# JPhan_Board3.net
KiCad netlist of a schematic drawn in EAGLE
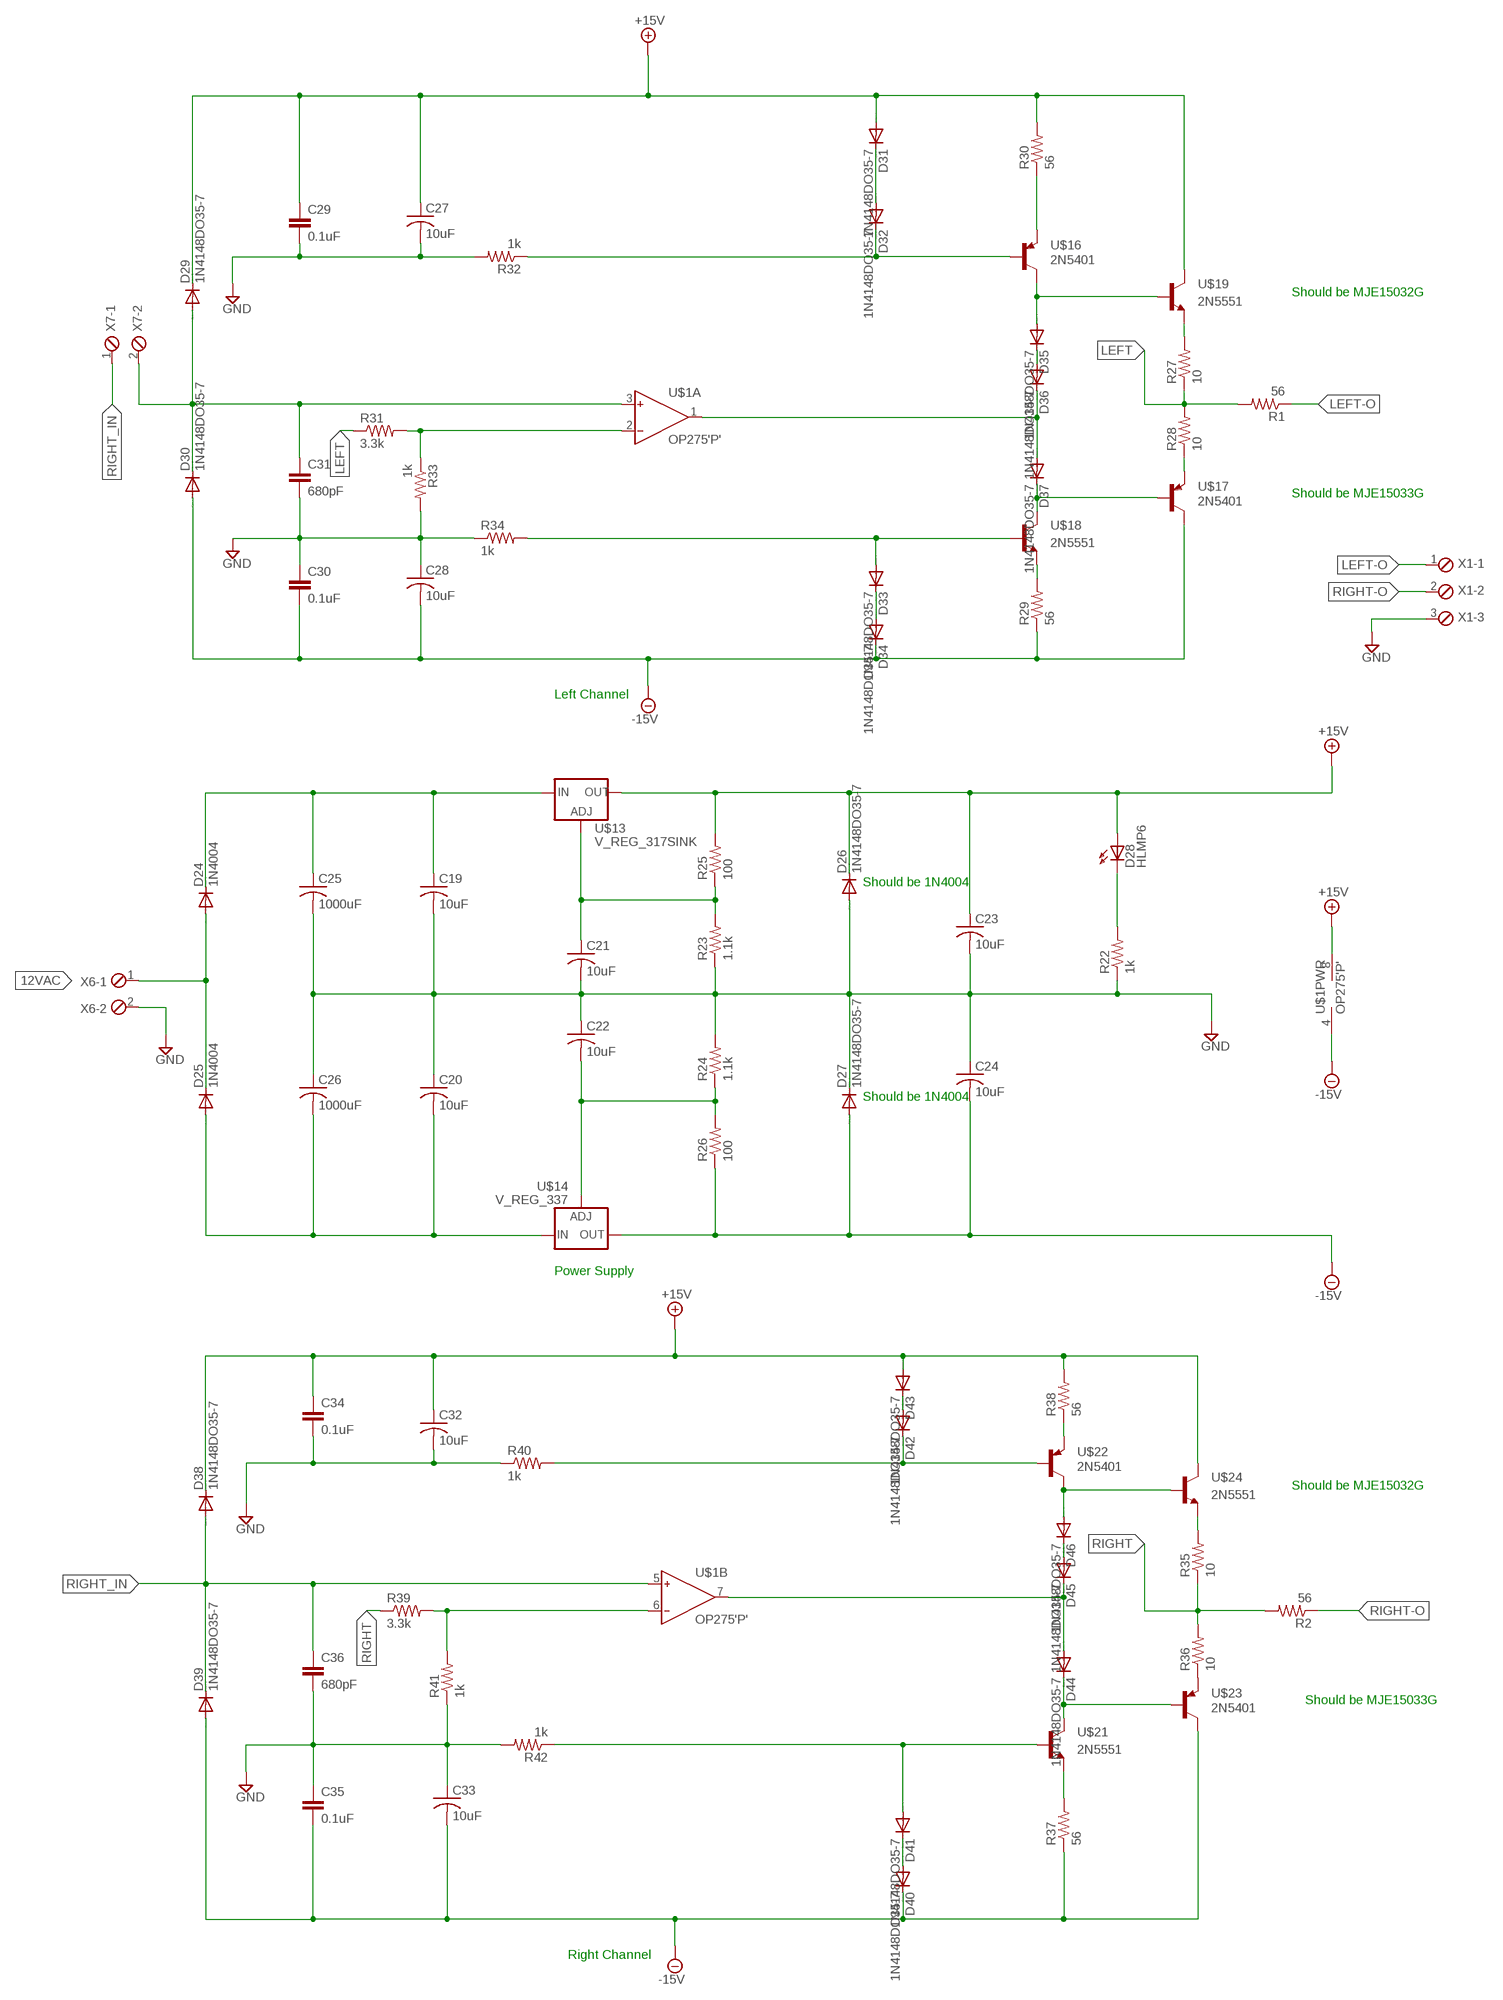
[diagram p0: schematic, sheet 1]

(export (version "E")
  (design (tool "Eeschema 10.0.6"))
  (components
    (comp (ref "C19")
      (value "10uF")
      (footprint "eagle-import:C025-030X050")
      (libsource (lib "eagle-import") (part "C-US025-030X050"))
    )
    (comp (ref "C20")
      (value "10uF")
      (footprint "eagle-import:C025-030X050")
      (libsource (lib "eagle-import") (part "C-US025-030X050"))
    )
    (comp (ref "C21")
      (value "10uF")
      (footprint "eagle-import:C025-030X050")
      (libsource (lib "eagle-import") (part "C-US025-030X050"))
    )
    (comp (ref "C22")
      (value "10uF")
      (footprint "eagle-import:C025-030X050")
      (libsource (lib "eagle-import") (part "C-US025-030X050"))
    )
    (comp (ref "C23")
      (value "10uF")
      (footprint "eagle-import:C025-030X050")
      (libsource (lib "eagle-import") (part "C-US025-030X050"))
    )
    (comp (ref "C24")
      (value "10uF")
      (footprint "eagle-import:C025-030X050")
      (libsource (lib "eagle-import") (part "C-US025-030X050"))
    )
    (comp (ref "C25")
      (value "1000uF")
      (footprint "eagle-import:C050-045X075")
      (libsource (lib "eagle-import") (part "C-US050-045X075"))
    )
    (comp (ref "C26")
      (value "1000uF")
      (footprint "eagle-import:C050-045X075")
      (libsource (lib "eagle-import") (part "C-US050-045X075"))
    )
    (comp (ref "C27")
      (value "10uF")
      (footprint "eagle-import:C025-030X050")
      (libsource (lib "eagle-import") (part "C-US025-030X050"))
    )
    (comp (ref "C28")
      (value "10uF")
      (footprint "eagle-import:C025-030X050")
      (libsource (lib "eagle-import") (part "C-US025-030X050"))
    )
    (comp (ref "C29")
      (value "0.1uF")
      (footprint "eagle-import:C025-024X044")
      (libsource (lib "eagle-import") (part "C-EU025-024X044"))
    )
    (comp (ref "C30")
      (value "0.1uF")
      (footprint "eagle-import:C025-024X044")
      (libsource (lib "eagle-import") (part "C-EU025-024X044"))
    )
    (comp (ref "C31")
      (value "680pF")
      (footprint "eagle-import:C025-024X044")
      (libsource (lib "eagle-import") (part "C-EU025-024X044"))
    )
    (comp (ref "C32")
      (value "10uF")
      (footprint "eagle-import:C025-030X050")
      (libsource (lib "eagle-import") (part "C-US025-030X050"))
    )
    (comp (ref "C33")
      (value "10uF")
      (footprint "eagle-import:C025-030X050")
      (libsource (lib "eagle-import") (part "C-US025-030X050"))
    )
    (comp (ref "C34")
      (value "0.1uF")
      (footprint "eagle-import:C025-024X044")
      (libsource (lib "eagle-import") (part "C-EU025-024X044"))
    )
    (comp (ref "C35")
      (value "0.1uF")
      (footprint "eagle-import:C025-024X044")
      (libsource (lib "eagle-import") (part "C-EU025-024X044"))
    )
    (comp (ref "C36")
      (value "680pF")
      (footprint "eagle-import:C025-024X044")
      (libsource (lib "eagle-import") (part "C-EU025-024X044"))
    )
    (comp (ref "D24")
      (value "1N4004")
      (footprint "eagle-import:DO41-10")
      (libsource (lib "eagle-import") (part "1N4004"))
    )
    (comp (ref "D25")
      (value "1N4004")
      (footprint "eagle-import:DO41-10")
      (libsource (lib "eagle-import") (part "1N4004"))
    )
    (comp (ref "D26")
      (value "1N4148DO35-7")
      (footprint "eagle-import:DO35-7")
      (libsource (lib "eagle-import") (part "1N4148DO35-7"))
    )
    (comp (ref "D27")
      (value "1N4148DO35-7")
      (footprint "eagle-import:DO35-7")
      (libsource (lib "eagle-import") (part "1N4148DO35-7"))
    )
    (comp (ref "D28")
      (value "HLMP6")
      (footprint "eagle-import:HLMP6")
      (fields (field (name "MF") "AGILENT TECHNOLOGIES") (field (name "MPN") "HLMP-6500"))
      (libsource (lib "eagle-import") (part "HLMP6"))
    )
    (comp (ref "D29")
      (value "1N4148DO35-7")
      (footprint "eagle-import:DO35-7")
      (libsource (lib "eagle-import") (part "1N4148DO35-7"))
    )
    (comp (ref "D30")
      (value "1N4148DO35-7")
      (footprint "eagle-import:DO35-7")
      (libsource (lib "eagle-import") (part "1N4148DO35-7"))
    )
    (comp (ref "D31")
      (value "1N4148DO35-7")
      (footprint "eagle-import:DO35-7")
      (libsource (lib "eagle-import") (part "1N4148DO35-7"))
    )
    (comp (ref "D32")
      (value "1N4148DO35-7")
      (footprint "eagle-import:DO35-7")
      (libsource (lib "eagle-import") (part "1N4148DO35-7"))
    )
    (comp (ref "D33")
      (value "1N4148DO35-7")
      (footprint "eagle-import:DO35-7")
      (libsource (lib "eagle-import") (part "1N4148DO35-7"))
    )
    (comp (ref "D34")
      (value "1N4148DO35-7")
      (footprint "eagle-import:DO35-7")
      (libsource (lib "eagle-import") (part "1N4148DO35-7"))
    )
    (comp (ref "D35")
      (value "1N4148DO35-7")
      (footprint "eagle-import:DO35-7")
      (libsource (lib "eagle-import") (part "1N4148DO35-7"))
    )
    (comp (ref "D36")
      (value "1N4148DO35-7")
      (footprint "eagle-import:DO35-7")
      (libsource (lib "eagle-import") (part "1N4148DO35-7"))
    )
    (comp (ref "D37")
      (value "1N4148DO35-7")
      (footprint "eagle-import:DO35-7")
      (libsource (lib "eagle-import") (part "1N4148DO35-7"))
    )
    (comp (ref "D38")
      (value "1N4148DO35-7")
      (footprint "eagle-import:DO35-7")
      (libsource (lib "eagle-import") (part "1N4148DO35-7"))
    )
    (comp (ref "D39")
      (value "1N4148DO35-7")
      (footprint "eagle-import:DO35-7")
      (libsource (lib "eagle-import") (part "1N4148DO35-7"))
    )
    (comp (ref "D40")
      (value "1N4148DO35-7")
      (footprint "eagle-import:DO35-7")
      (libsource (lib "eagle-import") (part "1N4148DO35-7"))
    )
    (comp (ref "D41")
      (value "1N4148DO35-7")
      (footprint "eagle-import:DO35-7")
      (libsource (lib "eagle-import") (part "1N4148DO35-7"))
    )
    (comp (ref "D42")
      (value "1N4148DO35-7")
      (footprint "eagle-import:DO35-7")
      (libsource (lib "eagle-import") (part "1N4148DO35-7"))
    )
    (comp (ref "D43")
      (value "1N4148DO35-7")
      (footprint "eagle-import:DO35-7")
      (libsource (lib "eagle-import") (part "1N4148DO35-7"))
    )
    (comp (ref "D44")
      (value "1N4148DO35-7")
      (footprint "eagle-import:DO35-7")
      (libsource (lib "eagle-import") (part "1N4148DO35-7"))
    )
    (comp (ref "D45")
      (value "1N4148DO35-7")
      (footprint "eagle-import:DO35-7")
      (libsource (lib "eagle-import") (part "1N4148DO35-7"))
    )
    (comp (ref "D46")
      (value "1N4148DO35-7")
      (footprint "eagle-import:DO35-7")
      (libsource (lib "eagle-import") (part "1N4148DO35-7"))
    )
    (comp (ref "R1")
      (value "56")
      (footprint "eagle-import:0204_7")
      (libsource (lib "eagle-import") (part "R-US_0204/7"))
    )
    (comp (ref "R2")
      (value "56")
      (footprint "eagle-import:0204_7")
      (libsource (lib "eagle-import") (part "R-US_0204/7"))
    )
    (comp (ref "R22")
      (value "1k")
      (footprint "eagle-import:0204_7")
      (libsource (lib "eagle-import") (part "R-US_0204/7"))
    )
    (comp (ref "R23")
      (value "1.1k")
      (footprint "eagle-import:0204_7")
      (libsource (lib "eagle-import") (part "R-US_0204/7"))
    )
    (comp (ref "R24")
      (value "1.1k")
      (footprint "eagle-import:0204_7")
      (libsource (lib "eagle-import") (part "R-US_0204/7"))
    )
    (comp (ref "R25")
      (value "100")
      (footprint "eagle-import:0204_7")
      (libsource (lib "eagle-import") (part "R-US_0204/7"))
    )
    (comp (ref "R26")
      (value "100")
      (footprint "eagle-import:0204_7")
      (libsource (lib "eagle-import") (part "R-US_0204/7"))
    )
    (comp (ref "R27")
      (value "10")
      (footprint "eagle-import:0204_7")
      (libsource (lib "eagle-import") (part "R-US_0204/7"))
    )
    (comp (ref "R28")
      (value "10")
      (footprint "eagle-import:0204_7")
      (libsource (lib "eagle-import") (part "R-US_0204/7"))
    )
    (comp (ref "R29")
      (value "56")
      (footprint "eagle-import:0204_7")
      (libsource (lib "eagle-import") (part "R-US_0204/7"))
    )
    (comp (ref "R30")
      (value "56")
      (footprint "eagle-import:0204_7")
      (libsource (lib "eagle-import") (part "R-US_0204/7"))
    )
    (comp (ref "R31")
      (value "3.3k")
      (footprint "eagle-import:0204_7")
      (libsource (lib "eagle-import") (part "R-US_0204/7"))
    )
    (comp (ref "R32")
      (value "1k")
      (footprint "eagle-import:0204_7")
      (libsource (lib "eagle-import") (part "R-US_0204/7"))
    )
    (comp (ref "R33")
      (value "1k")
      (footprint "eagle-import:0204_7")
      (libsource (lib "eagle-import") (part "R-US_0204/7"))
    )
    (comp (ref "R34")
      (value "1k")
      (footprint "eagle-import:0204_7")
      (libsource (lib "eagle-import") (part "R-US_0204/7"))
    )
    (comp (ref "R35")
      (value "10")
      (footprint "eagle-import:0204_7")
      (libsource (lib "eagle-import") (part "R-US_0204/7"))
    )
    (comp (ref "R36")
      (value "10")
      (footprint "eagle-import:0204_7")
      (libsource (lib "eagle-import") (part "R-US_0204/7"))
    )
    (comp (ref "R37")
      (value "56")
      (footprint "eagle-import:0204_7")
      (libsource (lib "eagle-import") (part "R-US_0204/7"))
    )
    (comp (ref "R38")
      (value "56")
      (footprint "eagle-import:0204_7")
      (libsource (lib "eagle-import") (part "R-US_0204/7"))
    )
    (comp (ref "R39")
      (value "3.3k")
      (footprint "eagle-import:0204_7")
      (libsource (lib "eagle-import") (part "R-US_0204/7"))
    )
    (comp (ref "R40")
      (value "1k")
      (footprint "eagle-import:0204_7")
      (libsource (lib "eagle-import") (part "R-US_0204/7"))
    )
    (comp (ref "R41")
      (value "1k")
      (footprint "eagle-import:0204_7")
      (libsource (lib "eagle-import") (part "R-US_0204/7"))
    )
    (comp (ref "R42")
      (value "1k")
      (footprint "eagle-import:0204_7")
      (libsource (lib "eagle-import") (part "R-US_0204/7"))
    )
    (comp (ref "U$1")
      (value "OP275'P'")
      (footprint "eagle-import:DIL08")
      (libsource (lib "eagle-import") (part "OP275'P'"))
    )
    (comp (ref "U$13")
      (value "V_REG_317SINK")
      (footprint "eagle-import:TO220-ADJ")
      (libsource (lib "eagle-import") (part "V_REG_317SINK"))
    )
    (comp (ref "U$14")
      (value "V_REG_337")
      (footprint "eagle-import:TO220-ADJ-NEG")
      (libsource (lib "eagle-import") (part "V_REG_337"))
    )
    (comp (ref "U$16")
      (value "2N5401")
      (footprint "eagle-import:2N5401")
      (libsource (lib "eagle-import") (part "2N5401"))
    )
    (comp (ref "U$17")
      (value "2N5401")
      (footprint "eagle-import:2N5401")
      (libsource (lib "eagle-import") (part "2N5401"))
    )
    (comp (ref "U$18")
      (value "2N5551")
      (footprint "eagle-import:2N5551")
      (libsource (lib "eagle-import") (part "2N5551"))
    )
    (comp (ref "U$19")
      (value "2N5551")
      (footprint "eagle-import:2N5551")
      (libsource (lib "eagle-import") (part "2N5551"))
    )
    (comp (ref "U$21")
      (value "2N5551")
      (footprint "eagle-import:2N5551")
      (libsource (lib "eagle-import") (part "2N5551"))
    )
    (comp (ref "U$22")
      (value "2N5401")
      (footprint "eagle-import:2N5401")
      (libsource (lib "eagle-import") (part "2N5401"))
    )
    (comp (ref "U$23")
      (value "2N5401")
      (footprint "eagle-import:2N5401")
      (libsource (lib "eagle-import") (part "2N5401"))
    )
    (comp (ref "U$24")
      (value "2N5551")
      (footprint "eagle-import:2N5551")
      (libsource (lib "eagle-import") (part "2N5551"))
    )
    (comp (ref "X1")
      (value "MPT3")
      (footprint "eagle-import:3POL254")
      (libsource (lib "eagle-import") (part "MPT3"))
    )
    (comp (ref "X6")
      (value "MPT2")
      (footprint "eagle-import:2POL254")
      (libsource (lib "eagle-import") (part "MPT2"))
    )
    (comp (ref "X7")
      (value "MPT2")
      (footprint "eagle-import:2POL254")
      (libsource (lib "eagle-import") (part "MPT2"))
    )
  )
  (nets
    (net (code "1") (name "+15V") (class "Default")
      (node (ref "C23") (pin "1") (pinfunction "1_1") (pintype "passive"))
      (node (ref "C27") (pin "1") (pinfunction "1_1") (pintype "passive"))
      (node (ref "C29") (pin "1") (pinfunction "1_1") (pintype "passive"))
      (node (ref "C32") (pin "1") (pinfunction "1_1") (pintype "passive"))
      (node (ref "C34") (pin "1") (pinfunction "1_1") (pintype "passive"))
      (node (ref "D26") (pin "C") (pinfunction "C_C") (pintype "passive"))
      (node (ref "D28") (pin "A") (pinfunction "A_A") (pintype "passive"))
      (node (ref "D29") (pin "C") (pinfunction "C_C") (pintype "passive"))
      (node (ref "D31") (pin "A") (pinfunction "A_A") (pintype "passive"))
      (node (ref "D38") (pin "C") (pinfunction "C_C") (pintype "passive"))
      (node (ref "D43") (pin "A") (pinfunction "A_A") (pintype "passive"))
      (node (ref "R25") (pin "2") (pinfunction "2_2") (pintype "passive"))
      (node (ref "R30") (pin "2") (pinfunction "2_2") (pintype "passive"))
      (node (ref "R38") (pin "2") (pinfunction "2_2") (pintype "passive"))
      (node (ref "U$1") (pin "8") (pinfunction "V+_8") (pintype "power_in"))
      (node (ref "U$13") (pin "OUT") (pinfunction "OUT_OUT") (pintype "output"))
      (node (ref "U$19") (pin "C") (pinfunction "C_C") (pintype "passive"))
      (node (ref "U$24") (pin "C") (pinfunction "C_C") (pintype "passive"))
    )
    (net (code "2") (name "-15V") (class "Default")
      (node (ref "C24") (pin "2") (pinfunction "2_2") (pintype "passive"))
      (node (ref "C28") (pin "2") (pinfunction "2_2") (pintype "passive"))
      (node (ref "C30") (pin "2") (pinfunction "2_2") (pintype "passive"))
      (node (ref "C33") (pin "2") (pinfunction "2_2") (pintype "passive"))
      (node (ref "C35") (pin "2") (pinfunction "2_2") (pintype "passive"))
      (node (ref "D27") (pin "A") (pinfunction "A_A") (pintype "passive"))
      (node (ref "D30") (pin "A") (pinfunction "A_A") (pintype "passive"))
      (node (ref "D34") (pin "C") (pinfunction "C_C") (pintype "passive"))
      (node (ref "D39") (pin "A") (pinfunction "A_A") (pintype "passive"))
      (node (ref "D40") (pin "C") (pinfunction "C_C") (pintype "passive"))
      (node (ref "R26") (pin "1") (pinfunction "1_1") (pintype "passive"))
      (node (ref "R29") (pin "1") (pinfunction "1_1") (pintype "passive"))
      (node (ref "R37") (pin "1") (pinfunction "1_1") (pintype "passive"))
      (node (ref "U$1") (pin "4") (pinfunction "V-_4") (pintype "power_in"))
      (node (ref "U$14") (pin "OUT") (pinfunction "OUT_OUT") (pintype "output"))
      (node (ref "U$17") (pin "C") (pinfunction "C_C") (pintype "passive"))
      (node (ref "U$23") (pin "C") (pinfunction "C_C") (pintype "passive"))
    )
    (net (code "3") (name "12VAC") (class "Default")
      (node (ref "D24") (pin "A") (pinfunction "A_A") (pintype "passive"))
      (node (ref "D25") (pin "C") (pinfunction "C_C") (pintype "passive"))
      (node (ref "X6") (pin "1") (pinfunction "1_1") (pintype "passive"))
    )
    (net (code "4") (name "GND") (class "Default")
      (node (ref "C19") (pin "2") (pinfunction "2_2") (pintype "passive"))
      (node (ref "C20") (pin "1") (pinfunction "1_1") (pintype "passive"))
      (node (ref "C21") (pin "2") (pinfunction "2_2") (pintype "passive"))
      (node (ref "C22") (pin "1") (pinfunction "1_1") (pintype "passive"))
      (node (ref "C23") (pin "2") (pinfunction "2_2") (pintype "passive"))
      (node (ref "C24") (pin "1") (pinfunction "1_1") (pintype "passive"))
      (node (ref "C25") (pin "2") (pinfunction "2_2") (pintype "passive"))
      (node (ref "C26") (pin "1") (pinfunction "1_1") (pintype "passive"))
      (node (ref "C27") (pin "2") (pinfunction "2_2") (pintype "passive"))
      (node (ref "C28") (pin "1") (pinfunction "1_1") (pintype "passive"))
      (node (ref "C29") (pin "2") (pinfunction "2_2") (pintype "passive"))
      (node (ref "C30") (pin "1") (pinfunction "1_1") (pintype "passive"))
      (node (ref "C31") (pin "2") (pinfunction "2_2") (pintype "passive"))
      (node (ref "C32") (pin "2") (pinfunction "2_2") (pintype "passive"))
      (node (ref "C33") (pin "1") (pinfunction "1_1") (pintype "passive"))
      (node (ref "C34") (pin "2") (pinfunction "2_2") (pintype "passive"))
      (node (ref "C35") (pin "1") (pinfunction "1_1") (pintype "passive"))
      (node (ref "C36") (pin "2") (pinfunction "2_2") (pintype "passive"))
      (node (ref "D26") (pin "A") (pinfunction "A_A") (pintype "passive"))
      (node (ref "D27") (pin "C") (pinfunction "C_C") (pintype "passive"))
      (node (ref "R22") (pin "1") (pinfunction "1_1") (pintype "passive"))
      (node (ref "R23") (pin "1") (pinfunction "1_1") (pintype "passive"))
      (node (ref "R24") (pin "2") (pinfunction "2_2") (pintype "passive"))
      (node (ref "R32") (pin "2") (pinfunction "2_2") (pintype "passive"))
      (node (ref "R33") (pin "2") (pinfunction "2_2") (pintype "passive"))
      (node (ref "R34") (pin "1") (pinfunction "1_1") (pintype "passive"))
      (node (ref "R40") (pin "1") (pinfunction "1_1") (pintype "passive"))
      (node (ref "R41") (pin "1") (pinfunction "1_1") (pintype "passive"))
      (node (ref "R42") (pin "2") (pinfunction "2_2") (pintype "passive"))
      (node (ref "X1") (pin "3") (pinfunction "1_3") (pintype "passive"))
      (node (ref "X6") (pin "2") (pinfunction "1_2") (pintype "passive"))
    )
    (net (code "5") (name "LEFT") (class "Default")
      (node (ref "R1") (pin "2") (pinfunction "2_2") (pintype "passive"))
      (node (ref "R27") (pin "1") (pinfunction "1_1") (pintype "passive"))
      (node (ref "R28") (pin "2") (pinfunction "2_2") (pintype "passive"))
      (node (ref "R31") (pin "1") (pinfunction "1_1") (pintype "passive"))
    )
    (net (code "6") (name "LEFT-O") (class "Default")
      (node (ref "R1") (pin "1") (pinfunction "1_1") (pintype "passive"))
      (node (ref "X1") (pin "1") (pinfunction "1_1") (pintype "passive"))
    )
    (net (code "7") (name "Net-(C19-Pad1)") (class "Default")
      (node (ref "C19") (pin "1") (pinfunction "1_1") (pintype "passive"))
      (node (ref "C25") (pin "1") (pinfunction "1_1") (pintype "passive"))
      (node (ref "D24") (pin "C") (pinfunction "C_C") (pintype "passive"))
      (node (ref "U$13") (pin "IN") (pinfunction "IN_IN") (pintype "input"))
    )
    (net (code "8") (name "Net-(C20-Pad2)") (class "Default")
      (node (ref "C20") (pin "2") (pinfunction "2_2") (pintype "passive"))
      (node (ref "C26") (pin "2") (pinfunction "2_2") (pintype "passive"))
      (node (ref "D25") (pin "A") (pinfunction "A_A") (pintype "passive"))
      (node (ref "U$14") (pin "IN") (pinfunction "IN_IN") (pintype "input"))
    )
    (net (code "9") (name "Net-(C21-Pad1)") (class "Default")
      (node (ref "C21") (pin "1") (pinfunction "1_1") (pintype "passive"))
      (node (ref "R23") (pin "2") (pinfunction "2_2") (pintype "passive"))
      (node (ref "R25") (pin "1") (pinfunction "1_1") (pintype "passive"))
      (node (ref "U$13") (pin "ADJ") (pinfunction "ADJ_ADJ") (pintype "input"))
    )
    (net (code "10") (name "Net-(C22-Pad2)") (class "Default")
      (node (ref "C22") (pin "2") (pinfunction "2_2") (pintype "passive"))
      (node (ref "R24") (pin "1") (pinfunction "1_1") (pintype "passive"))
      (node (ref "R26") (pin "2") (pinfunction "2_2") (pintype "passive"))
      (node (ref "U$14") (pin "ADJ") (pinfunction "ADJ_ADJ") (pintype "input"))
    )
    (net (code "11") (name "Net-(D28-PadK)") (class "Default")
      (node (ref "D28") (pin "K") (pinfunction "K_K") (pintype "passive"))
      (node (ref "R22") (pin "2") (pinfunction "2_2") (pintype "passive"))
    )
    (net (code "12") (name "Net-(D31-PadC)") (class "Default")
      (node (ref "D31") (pin "C") (pinfunction "C_C") (pintype "passive"))
      (node (ref "D32") (pin "A") (pinfunction "A_A") (pintype "passive"))
    )
    (net (code "13") (name "Net-(D32-PadC)") (class "Default")
      (node (ref "D32") (pin "C") (pinfunction "C_C") (pintype "passive"))
      (node (ref "R32") (pin "1") (pinfunction "1_1") (pintype "passive"))
      (node (ref "U$16") (pin "B") (pinfunction "B_B") (pintype "passive"))
    )
    (net (code "14") (name "Net-(D33-PadA)") (class "Default")
      (node (ref "D33") (pin "A") (pinfunction "A_A") (pintype "passive"))
      (node (ref "R34") (pin "2") (pinfunction "2_2") (pintype "passive"))
      (node (ref "U$18") (pin "B") (pinfunction "B_B") (pintype "passive"))
    )
    (net (code "15") (name "Net-(D33-PadC)") (class "Default")
      (node (ref "D33") (pin "C") (pinfunction "C_C") (pintype "passive"))
      (node (ref "D34") (pin "A") (pinfunction "A_A") (pintype "passive"))
    )
    (net (code "16") (name "Net-(D35-PadA)") (class "Default")
      (node (ref "D35") (pin "A") (pinfunction "A_A") (pintype "passive"))
      (node (ref "U$16") (pin "C") (pinfunction "C_C") (pintype "passive"))
      (node (ref "U$19") (pin "B") (pinfunction "B_B") (pintype "passive"))
    )
    (net (code "17") (name "Net-(D35-PadC)") (class "Default")
      (node (ref "D35") (pin "C") (pinfunction "C_C") (pintype "passive"))
      (node (ref "D36") (pin "A") (pinfunction "A_A") (pintype "passive"))
    )
    (net (code "18") (name "Net-(D37-PadC)") (class "Default")
      (node (ref "D37") (pin "C") (pinfunction "C_C") (pintype "passive"))
      (node (ref "U$17") (pin "B") (pinfunction "B_B") (pintype "passive"))
      (node (ref "U$18") (pin "C") (pinfunction "C_C") (pintype "passive"))
    )
    (net (code "19") (name "Net-(D40-PadA)") (class "Default")
      (node (ref "D40") (pin "A") (pinfunction "A_A") (pintype "passive"))
      (node (ref "D41") (pin "C") (pinfunction "C_C") (pintype "passive"))
    )
    (net (code "20") (name "Net-(D41-PadA)") (class "Default")
      (node (ref "D41") (pin "A") (pinfunction "A_A") (pintype "passive"))
      (node (ref "R42") (pin "1") (pinfunction "1_1") (pintype "passive"))
      (node (ref "U$21") (pin "B") (pinfunction "B_B") (pintype "passive"))
    )
    (net (code "21") (name "Net-(D42-PadA)") (class "Default")
      (node (ref "D42") (pin "A") (pinfunction "A_A") (pintype "passive"))
      (node (ref "D43") (pin "C") (pinfunction "C_C") (pintype "passive"))
    )
    (net (code "22") (name "Net-(D42-PadC)") (class "Default")
      (node (ref "D42") (pin "C") (pinfunction "C_C") (pintype "passive"))
      (node (ref "R40") (pin "2") (pinfunction "2_2") (pintype "passive"))
      (node (ref "U$22") (pin "B") (pinfunction "B_B") (pintype "passive"))
    )
    (net (code "23") (name "Net-(D44-PadC)") (class "Default")
      (node (ref "D44") (pin "C") (pinfunction "C_C") (pintype "passive"))
      (node (ref "U$21") (pin "C") (pinfunction "C_C") (pintype "passive"))
      (node (ref "U$23") (pin "B") (pinfunction "B_B") (pintype "passive"))
    )
    (net (code "24") (name "Net-(D45-PadA)") (class "Default")
      (node (ref "D45") (pin "A") (pinfunction "A_A") (pintype "passive"))
      (node (ref "D46") (pin "C") (pinfunction "C_C") (pintype "passive"))
    )
    (net (code "25") (name "Net-(D46-PadA)") (class "Default")
      (node (ref "D46") (pin "A") (pinfunction "A_A") (pintype "passive"))
      (node (ref "U$22") (pin "C") (pinfunction "C_C") (pintype "passive"))
      (node (ref "U$24") (pin "B") (pinfunction "B_B") (pintype "passive"))
    )
    (net (code "26") (name "Net-(R27-Pad2)") (class "Default")
      (node (ref "R27") (pin "2") (pinfunction "2_2") (pintype "passive"))
      (node (ref "U$19") (pin "E") (pinfunction "E_E") (pintype "passive"))
    )
    (net (code "27") (name "Net-(R28-Pad1)") (class "Default")
      (node (ref "R28") (pin "1") (pinfunction "1_1") (pintype "passive"))
      (node (ref "U$17") (pin "E") (pinfunction "E_E") (pintype "passive"))
    )
    (net (code "28") (name "Net-(R29-Pad2)") (class "Default")
      (node (ref "R29") (pin "2") (pinfunction "2_2") (pintype "passive"))
      (node (ref "U$18") (pin "E") (pinfunction "E_E") (pintype "passive"))
    )
    (net (code "29") (name "Net-(R30-Pad1)") (class "Default")
      (node (ref "R30") (pin "1") (pinfunction "1_1") (pintype "passive"))
      (node (ref "U$16") (pin "E") (pinfunction "E_E") (pintype "passive"))
    )
    (net (code "30") (name "Net-(R35-Pad2)") (class "Default")
      (node (ref "R35") (pin "2") (pinfunction "2_2") (pintype "passive"))
      (node (ref "U$24") (pin "E") (pinfunction "E_E") (pintype "passive"))
    )
    (net (code "31") (name "Net-(R36-Pad1)") (class "Default")
      (node (ref "R36") (pin "1") (pinfunction "1_1") (pintype "passive"))
      (node (ref "U$23") (pin "E") (pinfunction "E_E") (pintype "passive"))
    )
    (net (code "32") (name "Net-(R37-Pad2)") (class "Default")
      (node (ref "R37") (pin "2") (pinfunction "2_2") (pintype "passive"))
      (node (ref "U$21") (pin "E") (pinfunction "E_E") (pintype "passive"))
    )
    (net (code "33") (name "Net-(R38-Pad1)") (class "Default")
      (node (ref "R38") (pin "1") (pinfunction "1_1") (pintype "passive"))
      (node (ref "U$22") (pin "E") (pinfunction "E_E") (pintype "passive"))
    )
    (net (code "34") (name "Net-(U$1A-IN+)") (class "Default")
      (node (ref "C31") (pin "1") (pinfunction "1_1") (pintype "passive"))
      (node (ref "D29") (pin "A") (pinfunction "A_A") (pintype "passive"))
      (node (ref "D30") (pin "C") (pinfunction "C_C") (pintype "passive"))
      (node (ref "U$1") (pin "3") (pinfunction "IN+_3") (pintype "input"))
      (node (ref "X7") (pin "2") (pinfunction "1_2") (pintype "passive"))
    )
    (net (code "35") (name "Net-(U$1A-IN-)") (class "Default")
      (node (ref "R31") (pin "2") (pinfunction "2_2") (pintype "passive"))
      (node (ref "R33") (pin "1") (pinfunction "1_1") (pintype "passive"))
      (node (ref "U$1") (pin "2") (pinfunction "IN-_2") (pintype "input"))
    )
    (net (code "36") (name "Net-(U$1A-OUT)") (class "Default")
      (node (ref "D36") (pin "C") (pinfunction "C_C") (pintype "passive"))
      (node (ref "D37") (pin "A") (pinfunction "A_A") (pintype "passive"))
      (node (ref "U$1") (pin "1") (pinfunction "OUT_1") (pintype "output"))
    )
    (net (code "37") (name "Net-(U$1B-IN-)") (class "Default")
      (node (ref "R39") (pin "2") (pinfunction "2_2") (pintype "passive"))
      (node (ref "R41") (pin "2") (pinfunction "2_2") (pintype "passive"))
      (node (ref "U$1") (pin "6") (pinfunction "IN-_6") (pintype "input"))
    )
    (net (code "38") (name "Net-(U$1B-OUT)") (class "Default")
      (node (ref "D44") (pin "A") (pinfunction "A_A") (pintype "passive"))
      (node (ref "D45") (pin "C") (pinfunction "C_C") (pintype "passive"))
      (node (ref "U$1") (pin "7") (pinfunction "OUT_7") (pintype "output"))
    )
    (net (code "39") (name "RIGHT") (class "Default")
      (node (ref "R2") (pin "2") (pinfunction "2_2") (pintype "passive"))
      (node (ref "R35") (pin "1") (pinfunction "1_1") (pintype "passive"))
      (node (ref "R36") (pin "2") (pinfunction "2_2") (pintype "passive"))
      (node (ref "R39") (pin "1") (pinfunction "1_1") (pintype "passive"))
    )
    (net (code "40") (name "RIGHT-O") (class "Default")
      (node (ref "R2") (pin "1") (pinfunction "1_1") (pintype "passive"))
      (node (ref "X1") (pin "2") (pinfunction "1_2") (pintype "passive"))
    )
    (net (code "41") (name "RIGHT_IN") (class "Default")
      (node (ref "C36") (pin "1") (pinfunction "1_1") (pintype "passive"))
      (node (ref "D38") (pin "A") (pinfunction "A_A") (pintype "passive"))
      (node (ref "D39") (pin "C") (pinfunction "C_C") (pintype "passive"))
      (node (ref "U$1") (pin "5") (pinfunction "IN+_5") (pintype "input"))
      (node (ref "X7") (pin "1") (pinfunction "1_1") (pintype "passive"))
    )
  )
)
